# relay_Board.net
KiCad netlist of a schematic drawn in EAGLE
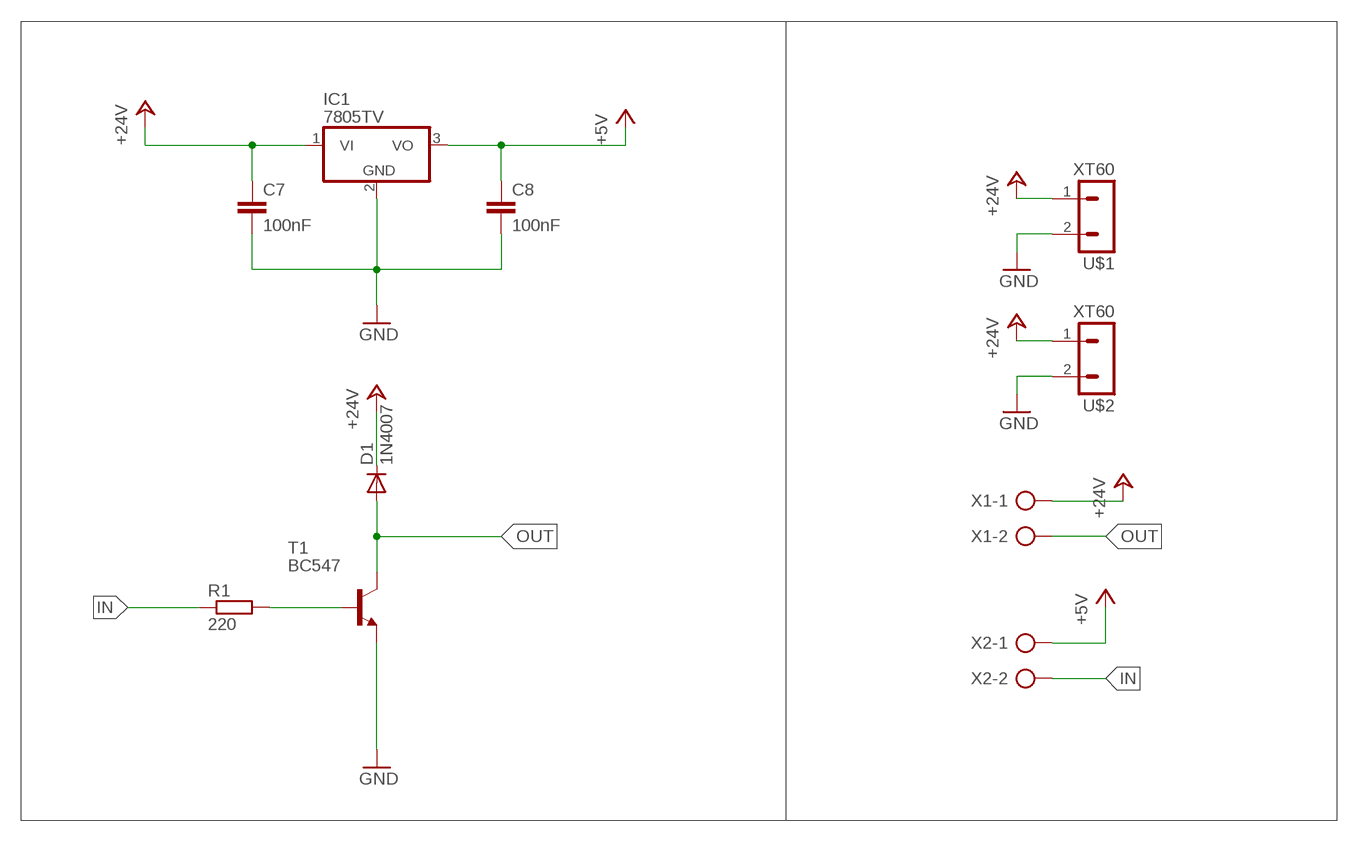
[diagram p0: schematic, sheet 1]

(export (version "E")
  (design (tool "Eeschema 10.0.6"))
  (components
    (comp (ref "C7")
      (value "100nF")
      (footprint "eagle-import:C5B5")
      (libsource (lib "eagle-import") (part "C5/5"))
    )
    (comp (ref "C8")
      (value "100nF")
      (footprint "eagle-import:C5B5")
      (libsource (lib "eagle-import") (part "C5/5"))
    )
    (comp (ref "D1")
      (value "1N4007")
      (footprint "eagle-import:DIODE")
      (libsource (lib "eagle-import") (part "DIODE"))
    )
    (comp (ref "IC1")
      (value "7805TV")
      (footprint "eagle-import:TO220V")
      (libsource (lib "eagle-import") (part "78TV05"))
    )
    (comp (ref "R1")
      (value "220")
      (footprint "eagle-import:0207_10")
      (libsource (lib "eagle-import") (part "RES"))
    )
    (comp (ref "T1")
      (value "BC547")
      (footprint "eagle-import:TO92")
      (libsource (lib "eagle-import") (part "BC547"))
    )
    (comp (ref "U$1")
      (value "XT60")
      (footprint "eagle-import:XT60")
      (libsource (lib "eagle-import") (part "XT60"))
    )
    (comp (ref "U$2")
      (value "XT60")
      (footprint "eagle-import:XT60")
      (libsource (lib "eagle-import") (part "XT60"))
    )
    (comp (ref "X1")
      (value "AK500/2")
      (footprint "eagle-import:AK500_2")
      (libsource (lib "eagle-import") (part "AK500/2"))
    )
    (comp (ref "X2")
      (value "AK500/2")
      (footprint "eagle-import:AK500_2")
      (libsource (lib "eagle-import") (part "AK500/2"))
    )
  )
  (nets
    (net (code "1") (name "+5V") (class "Default")
      (node (ref "C8") (pin "1") (pinfunction "1_1") (pintype "passive"))
      (node (ref "IC1") (pin "3") (pinfunction "VO_3") (pintype "passive"))
      (node (ref "X2") (pin "1") (pinfunction "KL_1") (pintype "passive"))
    )
    (net (code "2") (name "+24V") (class "Default")
      (node (ref "C7") (pin "1") (pinfunction "1_1") (pintype "passive"))
      (node (ref "D1") (pin "C") (pinfunction "C_C") (pintype "passive"))
      (node (ref "IC1") (pin "1") (pinfunction "VI_1") (pintype "input"))
      (node (ref "U$1") (pin "1") (pinfunction "1_1") (pintype "passive"))
      (node (ref "U$2") (pin "1") (pinfunction "1_1") (pintype "passive"))
      (node (ref "X1") (pin "1") (pinfunction "KL_1") (pintype "passive"))
    )
    (net (code "3") (name "GND") (class "Default")
      (node (ref "C7") (pin "2") (pinfunction "2_2") (pintype "passive"))
      (node (ref "C8") (pin "2") (pinfunction "2_2") (pintype "passive"))
      (node (ref "IC1") (pin "2") (pinfunction "GND_2") (pintype "passive"))
      (node (ref "T1") (pin "1") (pinfunction "E_1") (pintype "passive"))
      (node (ref "U$1") (pin "2") (pinfunction "2_2") (pintype "passive"))
      (node (ref "U$2") (pin "2") (pinfunction "2_2") (pintype "passive"))
    )
    (net (code "4") (name "IN") (class "Default")
      (node (ref "R1") (pin "1") (pinfunction "1_1") (pintype "passive"))
      (node (ref "X2") (pin "2") (pinfunction "KL_2") (pintype "passive"))
    )
    (net (code "5") (name "Net-(T1-B)") (class "Default")
      (node (ref "R1") (pin "2") (pinfunction "2_2") (pintype "passive"))
      (node (ref "T1") (pin "2") (pinfunction "B_2") (pintype "passive"))
    )
    (net (code "6") (name "OUT") (class "Default")
      (node (ref "D1") (pin "A") (pinfunction "A_A") (pintype "passive"))
      (node (ref "T1") (pin "3") (pinfunction "C_3") (pintype "passive"))
      (node (ref "X1") (pin "2") (pinfunction "KL_2") (pintype "passive"))
    )
  )
)
